# cpu_board.net
KiCad netlist of a schematic drawn in EAGLE
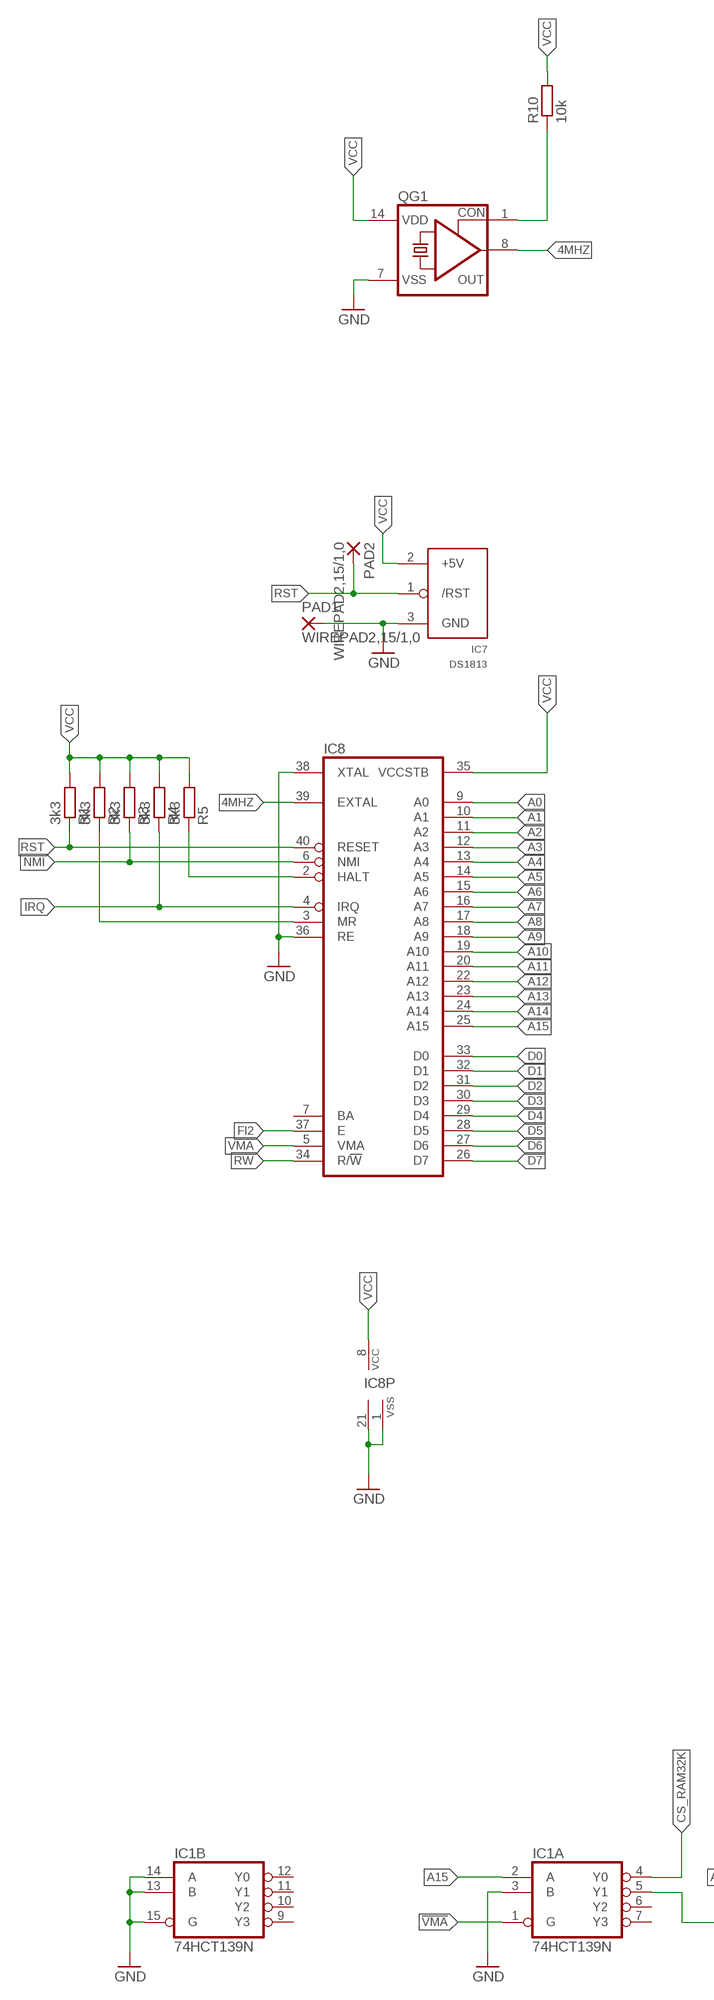
[diagram p0: schematic, sheet 1, part 1 of 2]
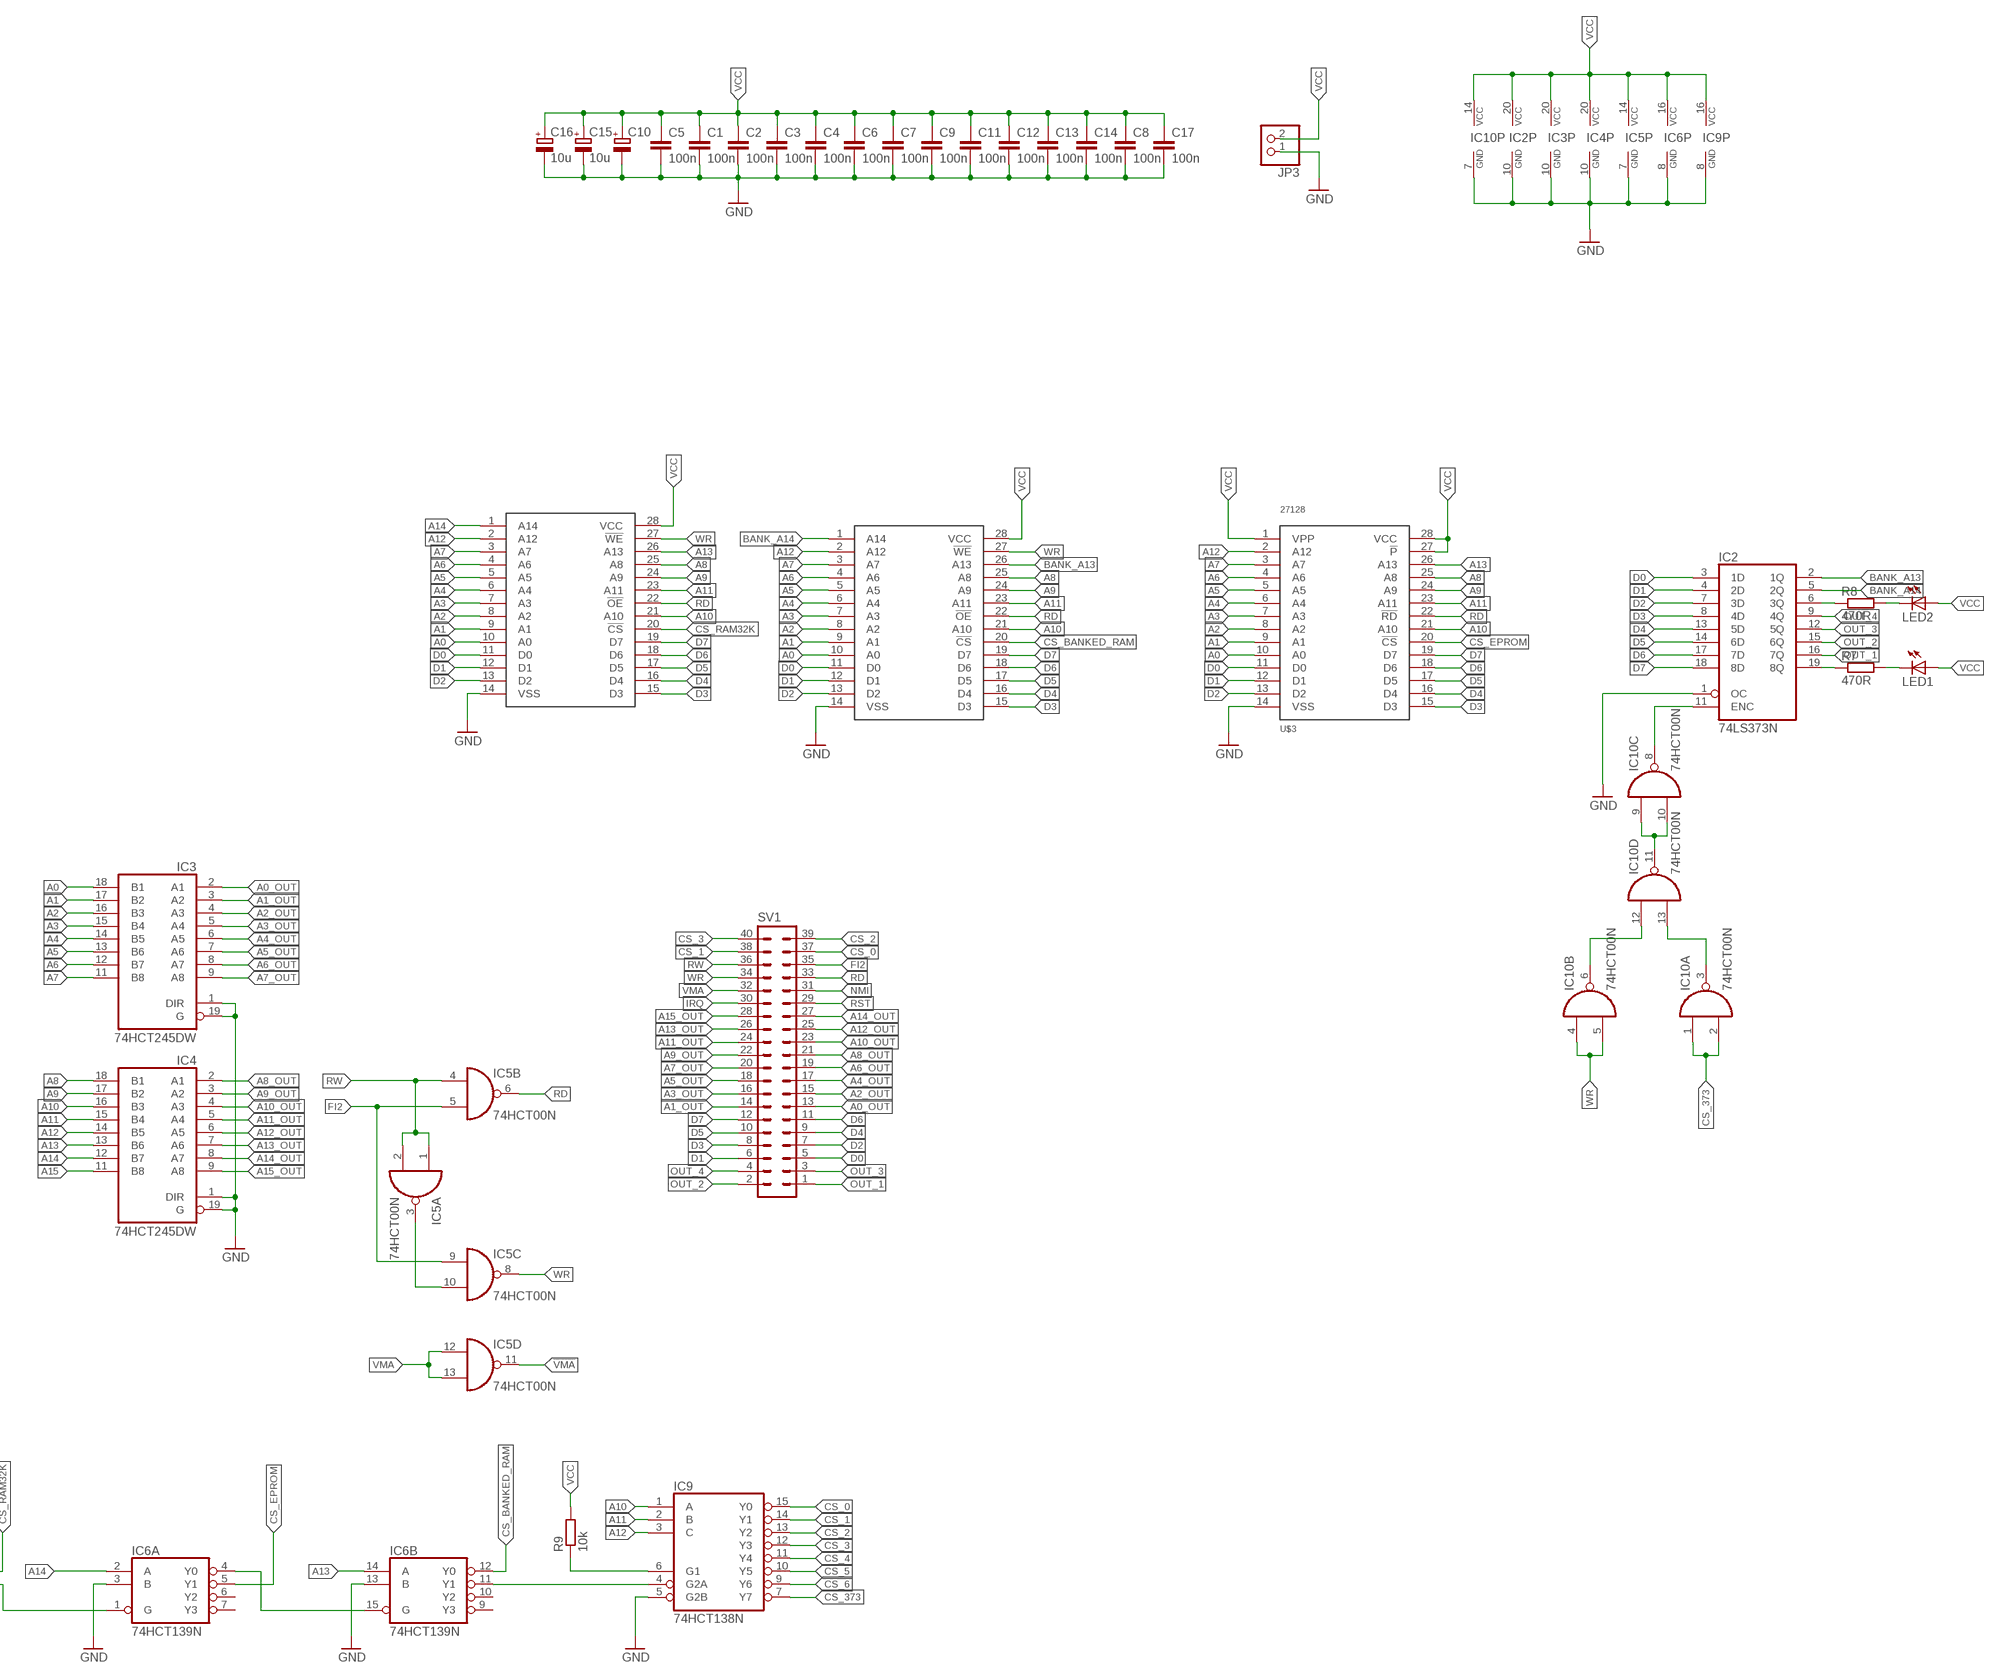
[diagram p1: schematic, sheet 1, part 2 of 2]

(export (version "E")
  (design (tool "Eeschema 10.0.6"))
  (components
    (comp (ref "C1")
      (value "100n")
      (footprint "eagle-import:C1206")
      (libsource (lib "eagle-import") (part "C-EUC1206"))
    )
    (comp (ref "C2")
      (value "100n")
      (footprint "eagle-import:C1206")
      (libsource (lib "eagle-import") (part "C-EUC1206"))
    )
    (comp (ref "C3")
      (value "100n")
      (footprint "eagle-import:C1206")
      (libsource (lib "eagle-import") (part "C-EUC1206"))
    )
    (comp (ref "C4")
      (value "100n")
      (footprint "eagle-import:C1206")
      (libsource (lib "eagle-import") (part "C-EUC1206"))
    )
    (comp (ref "C5")
      (value "100n")
      (footprint "eagle-import:C0603")
      (libsource (lib "eagle-import") (part "C-EUC0603"))
    )
    (comp (ref "C6")
      (value "100n")
      (footprint "eagle-import:C1206")
      (libsource (lib "eagle-import") (part "C-EUC1206"))
    )
    (comp (ref "C7")
      (value "100n")
      (footprint "eagle-import:C0603")
      (libsource (lib "eagle-import") (part "C-EUC0603"))
    )
    (comp (ref "C8")
      (value "100n")
      (footprint "eagle-import:C1206")
      (libsource (lib "eagle-import") (part "C-EUC1206"))
    )
    (comp (ref "C9")
      (value "100n")
      (footprint "eagle-import:C1206")
      (libsource (lib "eagle-import") (part "C-EUC1206"))
    )
    (comp (ref "C10")
      (value "CPOL-EUE5-10.5")
      (footprint "eagle-import:E5-10,5")
      (libsource (lib "eagle-import") (part "CPOL-EUE5-10.5"))
    )
    (comp (ref "C11")
      (value "100n")
      (footprint "eagle-import:C0805")
      (libsource (lib "eagle-import") (part "C-EUC0805"))
    )
    (comp (ref "C12")
      (value "100n")
      (footprint "eagle-import:C0805")
      (libsource (lib "eagle-import") (part "C-EUC0805"))
    )
    (comp (ref "C13")
      (value "100n")
      (footprint "eagle-import:C0805")
      (libsource (lib "eagle-import") (part "C-EUC0805"))
    )
    (comp (ref "C14")
      (value "100n")
      (footprint "eagle-import:C0603")
      (libsource (lib "eagle-import") (part "C-EUC0603"))
    )
    (comp (ref "C15")
      (value "10u")
      (footprint "eagle-import:SMC_B")
      (libsource (lib "eagle-import") (part "CPOL-EUSMCB"))
    )
    (comp (ref "C16")
      (value "10u")
      (footprint "eagle-import:SMC_B")
      (libsource (lib "eagle-import") (part "CPOL-EUSMCB"))
    )
    (comp (ref "C17")
      (value "100n")
      (footprint "eagle-import:C0805")
      (libsource (lib "eagle-import") (part "C-EUC0805"))
    )
    (comp (ref "IC1")
      (value "74HCT139N")
      (footprint "eagle-import:DIL16")
      (libsource (lib "eagle-import") (part "74139NHCT"))
    )
    (comp (ref "IC2")
      (value "74LS373N")
      (footprint "eagle-import:DIL20")
      (libsource (lib "eagle-import") (part "74373NLS"))
    )
    (comp (ref "IC3")
      (value "74HCT245DW")
      (footprint "eagle-import:SO20W")
      (libsource (lib "eagle-import") (part "74245DWHCT"))
    )
    (comp (ref "IC4")
      (value "74HCT245DW")
      (footprint "eagle-import:SO20W")
      (libsource (lib "eagle-import") (part "74245DWHCT"))
    )
    (comp (ref "IC5")
      (value "74HCT00N")
      (footprint "eagle-import:DIL14")
      (libsource (lib "eagle-import") (part "7400NHCT"))
    )
    (comp (ref "IC6")
      (value "74HCT139N")
      (footprint "eagle-import:DIL16")
      (libsource (lib "eagle-import") (part "74139NHCT"))
    )
    (comp (ref "IC7")
      (value "DS1813")
      (footprint "eagle-import:TO-92")
      (libsource (lib "eagle-import") (part "DS1813"))
    )
    (comp (ref "IC8")
      (value "6802")
      (footprint "eagle-import:DIL40")
      (libsource (lib "eagle-import") (part "6802"))
    )
    (comp (ref "IC9")
      (value "74HCT138N")
      (footprint "eagle-import:DIL16")
      (libsource (lib "eagle-import") (part "74138NHCT"))
    )
    (comp (ref "IC10")
      (value "74HCT00N")
      (footprint "eagle-import:DIL14")
      (libsource (lib "eagle-import") (part "7400NHCT"))
    )
    (comp (ref "JP3")
      (value "PINHD-1X2/90")
      (footprint "eagle-import:1X02_90")
      (libsource (lib "eagle-import") (part "PINHD-1X2/90"))
    )
    (comp (ref "LED1")
      (value "LED5MM")
      (footprint "eagle-import:LED5MM")
      (libsource (lib "eagle-import") (part "LED5MM"))
    )
    (comp (ref "LED2")
      (value "LED5MM")
      (footprint "eagle-import:LED5MM")
      (libsource (lib "eagle-import") (part "LED5MM"))
    )
    (comp (ref "PAD1")
      (value "WIREPAD2,15/1,0")
      (footprint "eagle-import:2,15_1,0")
      (libsource (lib "eagle-import") (part "WIREPAD2,15/1,0"))
    )
    (comp (ref "PAD2")
      (value "WIREPAD2,15/1,0")
      (footprint "eagle-import:2,15_1,0")
      (libsource (lib "eagle-import") (part "WIREPAD2,15/1,0"))
    )
    (comp (ref "QG1")
      (value "CRYSTAL_RES-SG51")
      (footprint "eagle-import:SG51")
      (libsource (lib "eagle-import") (part "CRYSTAL_RES-SG51"))
    )
    (comp (ref "R1")
      (value "3k3")
      (footprint "eagle-import:R1206")
      (libsource (lib "eagle-import") (part "R-EU_R1206"))
    )
    (comp (ref "R2")
      (value "3k3")
      (footprint "eagle-import:R1206")
      (libsource (lib "eagle-import") (part "R-EU_R1206"))
    )
    (comp (ref "R3")
      (value "3k3")
      (footprint "eagle-import:R1206")
      (libsource (lib "eagle-import") (part "R-EU_R1206"))
    )
    (comp (ref "R4")
      (value "3k3")
      (footprint "eagle-import:R0603")
      (libsource (lib "eagle-import") (part "R-EU_R0603"))
    )
    (comp (ref "R5")
      (value "3k3")
      (footprint "eagle-import:R1206")
      (libsource (lib "eagle-import") (part "R-EU_R1206"))
    )
    (comp (ref "R7")
      (value "470R")
      (footprint "eagle-import:R1206")
      (libsource (lib "eagle-import") (part "R-EU_R1206"))
    )
    (comp (ref "R8")
      (value "470R")
      (footprint "eagle-import:R1206")
      (libsource (lib "eagle-import") (part "R-EU_R1206"))
    )
    (comp (ref "R9")
      (value "10k")
      (footprint "eagle-import:0204_7")
      (libsource (lib "eagle-import") (part "R-EU_0204/7"))
    )
    (comp (ref "R10")
      (value "10k")
      (footprint "eagle-import:R1206")
      (libsource (lib "eagle-import") (part "R-EU_R1206"))
    )
    (comp (ref "SV1")
      (value "ML40L")
      (footprint "eagle-import:ML40L")
      (libsource (lib "eagle-import") (part "ML40L"))
    )
    (comp (ref "U$2")
      (value "62256")
      (footprint "eagle-import:DIL28-6")
      (libsource (lib "eagle-import") (part "62256"))
    )
    (comp (ref "U$3")
      (value "27128")
      (footprint "eagle-import:DIL28")
      (libsource (lib "eagle-import") (part "27128"))
    )
    (comp (ref "U$4")
      (value "62256")
      (footprint "eagle-import:DIL28-6")
      (libsource (lib "eagle-import") (part "62256"))
    )
  )
  (nets
    (net (code "1") (name "/~{VMA}") (class "Default")
      (node (ref "IC1") (pin "1") (pinfunction "G_1") (pintype "input"))
      (node (ref "IC5") (pin "11") (pinfunction "O_11") (pintype "output"))
    )
    (net (code "2") (name "4MHZ") (class "Default")
      (node (ref "IC8") (pin "39") (pinfunction "EXTAL_39") (pintype "input"))
      (node (ref "QG1") (pin "8") (pinfunction "OUT_8") (pintype "output"))
    )
    (net (code "3") (name "A0") (class "Default")
      (node (ref "IC3") (pin "18") (pinfunction "B1_18") (pintype "bidirectional"))
      (node (ref "IC8") (pin "9") (pinfunction "A0_9") (pintype "output"))
      (node (ref "U$2") (pin "10") (pinfunction "A0_10") (pintype "bidirectional"))
      (node (ref "U$3") (pin "10") (pinfunction "A0_10") (pintype "bidirectional"))
      (node (ref "U$4") (pin "10") (pinfunction "A0_10") (pintype "bidirectional"))
    )
    (net (code "4") (name "A0_OUT") (class "Default")
      (node (ref "IC3") (pin "2") (pinfunction "A1_2") (pintype "bidirectional"))
      (node (ref "SV1") (pin "13") (pinfunction "13_13") (pintype "passive"))
    )
    (net (code "5") (name "A1") (class "Default")
      (node (ref "IC3") (pin "17") (pinfunction "B2_17") (pintype "bidirectional"))
      (node (ref "IC8") (pin "10") (pinfunction "A1_10") (pintype "output"))
      (node (ref "U$2") (pin "9") (pinfunction "A1_9") (pintype "bidirectional"))
      (node (ref "U$3") (pin "9") (pinfunction "A1_9") (pintype "bidirectional"))
      (node (ref "U$4") (pin "9") (pinfunction "A1_9") (pintype "bidirectional"))
    )
    (net (code "6") (name "A1_OUT") (class "Default")
      (node (ref "IC3") (pin "3") (pinfunction "A2_3") (pintype "bidirectional"))
      (node (ref "SV1") (pin "14") (pinfunction "14_14") (pintype "passive"))
    )
    (net (code "7") (name "A2") (class "Default")
      (node (ref "IC3") (pin "16") (pinfunction "B3_16") (pintype "bidirectional"))
      (node (ref "IC8") (pin "11") (pinfunction "A2_11") (pintype "output"))
      (node (ref "U$2") (pin "8") (pinfunction "A2_8") (pintype "bidirectional"))
      (node (ref "U$3") (pin "8") (pinfunction "A2_8") (pintype "bidirectional"))
      (node (ref "U$4") (pin "8") (pinfunction "A2_8") (pintype "bidirectional"))
    )
    (net (code "8") (name "A2_OUT") (class "Default")
      (node (ref "IC3") (pin "4") (pinfunction "A3_4") (pintype "bidirectional"))
      (node (ref "SV1") (pin "15") (pinfunction "15_15") (pintype "passive"))
    )
    (net (code "9") (name "A3") (class "Default")
      (node (ref "IC3") (pin "15") (pinfunction "B4_15") (pintype "bidirectional"))
      (node (ref "IC8") (pin "12") (pinfunction "A3_12") (pintype "output"))
      (node (ref "U$2") (pin "7") (pinfunction "A3_7") (pintype "bidirectional"))
      (node (ref "U$3") (pin "7") (pinfunction "A3_7") (pintype "bidirectional"))
      (node (ref "U$4") (pin "7") (pinfunction "A3_7") (pintype "bidirectional"))
    )
    (net (code "10") (name "A3_OUT") (class "Default")
      (node (ref "IC3") (pin "5") (pinfunction "A4_5") (pintype "bidirectional"))
      (node (ref "SV1") (pin "16") (pinfunction "16_16") (pintype "passive"))
    )
    (net (code "11") (name "A4") (class "Default")
      (node (ref "IC3") (pin "14") (pinfunction "B5_14") (pintype "bidirectional"))
      (node (ref "IC8") (pin "13") (pinfunction "A4_13") (pintype "output"))
      (node (ref "U$2") (pin "6") (pinfunction "A4_6") (pintype "bidirectional"))
      (node (ref "U$3") (pin "6") (pinfunction "A4_6") (pintype "bidirectional"))
      (node (ref "U$4") (pin "6") (pinfunction "A4_6") (pintype "bidirectional"))
    )
    (net (code "12") (name "A4_OUT") (class "Default")
      (node (ref "IC3") (pin "6") (pinfunction "A5_6") (pintype "bidirectional"))
      (node (ref "SV1") (pin "17") (pinfunction "17_17") (pintype "passive"))
    )
    (net (code "13") (name "A5") (class "Default")
      (node (ref "IC3") (pin "13") (pinfunction "B6_13") (pintype "bidirectional"))
      (node (ref "IC8") (pin "14") (pinfunction "A5_14") (pintype "output"))
      (node (ref "U$2") (pin "5") (pinfunction "A5_5") (pintype "bidirectional"))
      (node (ref "U$3") (pin "5") (pinfunction "A5_5") (pintype "bidirectional"))
      (node (ref "U$4") (pin "5") (pinfunction "A5_5") (pintype "bidirectional"))
    )
    (net (code "14") (name "A5_OUT") (class "Default")
      (node (ref "IC3") (pin "7") (pinfunction "A6_7") (pintype "bidirectional"))
      (node (ref "SV1") (pin "18") (pinfunction "18_18") (pintype "passive"))
    )
    (net (code "15") (name "A6") (class "Default")
      (node (ref "IC3") (pin "12") (pinfunction "B7_12") (pintype "bidirectional"))
      (node (ref "IC8") (pin "15") (pinfunction "A6_15") (pintype "output"))
      (node (ref "U$2") (pin "4") (pinfunction "A6_4") (pintype "bidirectional"))
      (node (ref "U$3") (pin "4") (pinfunction "A6_4") (pintype "bidirectional"))
      (node (ref "U$4") (pin "4") (pinfunction "A6_4") (pintype "bidirectional"))
    )
    (net (code "16") (name "A6_OUT") (class "Default")
      (node (ref "IC3") (pin "8") (pinfunction "A7_8") (pintype "bidirectional"))
      (node (ref "SV1") (pin "19") (pinfunction "19_19") (pintype "passive"))
    )
    (net (code "17") (name "A7") (class "Default")
      (node (ref "IC3") (pin "11") (pinfunction "B8_11") (pintype "bidirectional"))
      (node (ref "IC8") (pin "16") (pinfunction "A7_16") (pintype "output"))
      (node (ref "U$2") (pin "3") (pinfunction "A7_3") (pintype "bidirectional"))
      (node (ref "U$3") (pin "3") (pinfunction "A7_3") (pintype "bidirectional"))
      (node (ref "U$4") (pin "3") (pinfunction "A7_3") (pintype "bidirectional"))
    )
    (net (code "18") (name "A7_OUT") (class "Default")
      (node (ref "IC3") (pin "9") (pinfunction "A8_9") (pintype "bidirectional"))
      (node (ref "SV1") (pin "20") (pinfunction "20_20") (pintype "passive"))
    )
    (net (code "19") (name "A8") (class "Default")
      (node (ref "IC4") (pin "18") (pinfunction "B1_18") (pintype "bidirectional"))
      (node (ref "IC8") (pin "17") (pinfunction "A8_17") (pintype "output"))
      (node (ref "U$2") (pin "25") (pinfunction "A8_25") (pintype "bidirectional"))
      (node (ref "U$3") (pin "25") (pinfunction "A8_25") (pintype "bidirectional"))
      (node (ref "U$4") (pin "25") (pinfunction "A8_25") (pintype "bidirectional"))
    )
    (net (code "20") (name "A8_OUT") (class "Default")
      (node (ref "IC4") (pin "2") (pinfunction "A1_2") (pintype "bidirectional"))
      (node (ref "SV1") (pin "21") (pinfunction "21_21") (pintype "passive"))
    )
    (net (code "21") (name "A9") (class "Default")
      (node (ref "IC4") (pin "17") (pinfunction "B2_17") (pintype "bidirectional"))
      (node (ref "IC8") (pin "18") (pinfunction "A9_18") (pintype "output"))
      (node (ref "U$2") (pin "24") (pinfunction "A9_24") (pintype "bidirectional"))
      (node (ref "U$3") (pin "24") (pinfunction "A9_24") (pintype "bidirectional"))
      (node (ref "U$4") (pin "24") (pinfunction "A9_24") (pintype "bidirectional"))
    )
    (net (code "22") (name "A9_OUT") (class "Default")
      (node (ref "IC4") (pin "3") (pinfunction "A2_3") (pintype "bidirectional"))
      (node (ref "SV1") (pin "22") (pinfunction "22_22") (pintype "passive"))
    )
    (net (code "23") (name "A10") (class "Default")
      (node (ref "IC4") (pin "16") (pinfunction "B3_16") (pintype "bidirectional"))
      (node (ref "IC8") (pin "19") (pinfunction "A10_19") (pintype "output"))
      (node (ref "IC9") (pin "1") (pinfunction "A_1") (pintype "input"))
      (node (ref "U$2") (pin "21") (pinfunction "A10_21") (pintype "bidirectional"))
      (node (ref "U$3") (pin "21") (pinfunction "A10_21") (pintype "bidirectional"))
      (node (ref "U$4") (pin "21") (pinfunction "A10_21") (pintype "bidirectional"))
    )
    (net (code "24") (name "A10_OUT") (class "Default")
      (node (ref "IC4") (pin "4") (pinfunction "A3_4") (pintype "bidirectional"))
      (node (ref "SV1") (pin "23") (pinfunction "23_23") (pintype "passive"))
    )
    (net (code "25") (name "A11") (class "Default")
      (node (ref "IC4") (pin "15") (pinfunction "B4_15") (pintype "bidirectional"))
      (node (ref "IC8") (pin "20") (pinfunction "A11_20") (pintype "output"))
      (node (ref "IC9") (pin "2") (pinfunction "B_2") (pintype "input"))
      (node (ref "U$2") (pin "23") (pinfunction "A11_23") (pintype "bidirectional"))
      (node (ref "U$3") (pin "23") (pinfunction "A11_23") (pintype "bidirectional"))
      (node (ref "U$4") (pin "23") (pinfunction "A11_23") (pintype "bidirectional"))
    )
    (net (code "26") (name "A11_OUT") (class "Default")
      (node (ref "IC4") (pin "5") (pinfunction "A4_5") (pintype "bidirectional"))
      (node (ref "SV1") (pin "24") (pinfunction "24_24") (pintype "passive"))
    )
    (net (code "27") (name "A12") (class "Default")
      (node (ref "IC4") (pin "14") (pinfunction "B5_14") (pintype "bidirectional"))
      (node (ref "IC8") (pin "22") (pinfunction "A12_22") (pintype "output"))
      (node (ref "IC9") (pin "3") (pinfunction "C_3") (pintype "input"))
      (node (ref "U$2") (pin "2") (pinfunction "A12_2") (pintype "bidirectional"))
      (node (ref "U$3") (pin "2") (pinfunction "A12_2") (pintype "bidirectional"))
      (node (ref "U$4") (pin "2") (pinfunction "A12_2") (pintype "bidirectional"))
    )
    (net (code "28") (name "A12_OUT") (class "Default")
      (node (ref "IC4") (pin "6") (pinfunction "A5_6") (pintype "bidirectional"))
      (node (ref "SV1") (pin "25") (pinfunction "25_25") (pintype "passive"))
    )
    (net (code "29") (name "A13") (class "Default")
      (node (ref "IC4") (pin "13") (pinfunction "B6_13") (pintype "bidirectional"))
      (node (ref "IC6") (pin "14") (pinfunction "A_14") (pintype "input"))
      (node (ref "IC8") (pin "23") (pinfunction "A13_23") (pintype "output"))
      (node (ref "U$3") (pin "26") (pinfunction "A13_26") (pintype "bidirectional"))
      (node (ref "U$4") (pin "26") (pinfunction "A13_26") (pintype "bidirectional"))
    )
    (net (code "30") (name "A13_OUT") (class "Default")
      (node (ref "IC4") (pin "7") (pinfunction "A6_7") (pintype "bidirectional"))
      (node (ref "SV1") (pin "26") (pinfunction "26_26") (pintype "passive"))
    )
    (net (code "31") (name "A14") (class "Default")
      (node (ref "IC4") (pin "12") (pinfunction "B7_12") (pintype "bidirectional"))
      (node (ref "IC6") (pin "2") (pinfunction "A_2") (pintype "input"))
      (node (ref "IC8") (pin "24") (pinfunction "A14_24") (pintype "output"))
      (node (ref "U$4") (pin "1") (pinfunction "A14_1") (pintype "bidirectional"))
    )
    (net (code "32") (name "A14_OUT") (class "Default")
      (node (ref "IC4") (pin "8") (pinfunction "A7_8") (pintype "bidirectional"))
      (node (ref "SV1") (pin "27") (pinfunction "27_27") (pintype "passive"))
    )
    (net (code "33") (name "A15") (class "Default")
      (node (ref "IC1") (pin "2") (pinfunction "A_2") (pintype "input"))
      (node (ref "IC4") (pin "11") (pinfunction "B8_11") (pintype "bidirectional"))
      (node (ref "IC8") (pin "25") (pinfunction "A15_25") (pintype "output"))
    )
    (net (code "34") (name "A15_OUT") (class "Default")
      (node (ref "IC4") (pin "9") (pinfunction "A8_9") (pintype "bidirectional"))
      (node (ref "SV1") (pin "28") (pinfunction "28_28") (pintype "passive"))
    )
    (net (code "35") (name "BANK_A13") (class "Default")
      (node (ref "IC2") (pin "2") (pinfunction "1Q_2") (pintype "tri_state"))
      (node (ref "U$2") (pin "26") (pinfunction "A13_26") (pintype "bidirectional"))
    )
    (net (code "36") (name "BANK_A14") (class "Default")
      (node (ref "IC2") (pin "5") (pinfunction "2Q_5") (pintype "tri_state"))
      (node (ref "U$2") (pin "1") (pinfunction "A14_1") (pintype "bidirectional"))
    )
    (net (code "37") (name "CS_0") (class "Default")
      (node (ref "IC9") (pin "15") (pinfunction "Y0_15") (pintype "output"))
      (node (ref "SV1") (pin "37") (pinfunction "37_37") (pintype "passive"))
    )
    (net (code "38") (name "CS_1") (class "Default")
      (node (ref "IC9") (pin "14") (pinfunction "Y1_14") (pintype "output"))
      (node (ref "SV1") (pin "38") (pinfunction "38_38") (pintype "passive"))
    )
    (net (code "39") (name "CS_2") (class "Default")
      (node (ref "IC9") (pin "13") (pinfunction "Y2_13") (pintype "output"))
      (node (ref "SV1") (pin "39") (pinfunction "39_39") (pintype "passive"))
    )
    (net (code "40") (name "CS_3") (class "Default")
      (node (ref "IC9") (pin "12") (pinfunction "Y3_12") (pintype "output"))
      (node (ref "SV1") (pin "40") (pinfunction "40_40") (pintype "passive"))
    )
    (net (code "41") (name "CS_4") (class "Default")
      (node (ref "IC9") (pin "11") (pinfunction "Y4_11") (pintype "output"))
    )
    (net (code "42") (name "CS_5") (class "Default")
      (node (ref "IC9") (pin "10") (pinfunction "Y5_10") (pintype "output"))
    )
    (net (code "43") (name "CS_6") (class "Default")
      (node (ref "IC9") (pin "9") (pinfunction "Y6_9") (pintype "output"))
    )
    (net (code "44") (name "CS_373") (class "Default")
      (node (ref "IC10") (pin "1") (pinfunction "I0_1") (pintype "input"))
      (node (ref "IC10") (pin "2") (pinfunction "I1_2") (pintype "input"))
      (node (ref "IC9") (pin "7") (pinfunction "Y7_7") (pintype "output"))
    )
    (net (code "45") (name "CS_BANKED_RAM") (class "Default")
      (node (ref "IC6") (pin "12") (pinfunction "Y0_12") (pintype "output"))
      (node (ref "U$2") (pin "20") (pinfunction "~{CS}_20") (pintype "bidirectional"))
    )
    (net (code "46") (name "CS_EPROM") (class "Default")
      (node (ref "IC6") (pin "5") (pinfunction "Y1_5") (pintype "output"))
      (node (ref "U$3") (pin "20") (pinfunction "~{CS}_20") (pintype "bidirectional"))
    )
    (net (code "47") (name "CS_RAM32K") (class "Default")
      (node (ref "IC1") (pin "4") (pinfunction "Y0_4") (pintype "output"))
      (node (ref "U$4") (pin "20") (pinfunction "~{CS}_20") (pintype "bidirectional"))
    )
    (net (code "48") (name "D0") (class "Default")
      (node (ref "IC2") (pin "3") (pinfunction "1D_3") (pintype "input"))
      (node (ref "IC8") (pin "33") (pinfunction "D0_33") (pintype "bidirectional"))
      (node (ref "SV1") (pin "5") (pinfunction "5_5") (pintype "passive"))
      (node (ref "U$2") (pin "11") (pinfunction "D0_11") (pintype "bidirectional"))
      (node (ref "U$3") (pin "11") (pinfunction "D0_11") (pintype "bidirectional"))
      (node (ref "U$4") (pin "11") (pinfunction "D0_11") (pintype "bidirectional"))
    )
    (net (code "49") (name "D1") (class "Default")
      (node (ref "IC2") (pin "4") (pinfunction "2D_4") (pintype "input"))
      (node (ref "IC8") (pin "32") (pinfunction "D1_32") (pintype "bidirectional"))
      (node (ref "SV1") (pin "6") (pinfunction "6_6") (pintype "passive"))
      (node (ref "U$2") (pin "12") (pinfunction "D1_12") (pintype "bidirectional"))
      (node (ref "U$3") (pin "12") (pinfunction "D1_12") (pintype "bidirectional"))
      (node (ref "U$4") (pin "12") (pinfunction "D1_12") (pintype "bidirectional"))
    )
    (net (code "50") (name "D2") (class "Default")
      (node (ref "IC2") (pin "7") (pinfunction "3D_7") (pintype "input"))
      (node (ref "IC8") (pin "31") (pinfunction "D2_31") (pintype "bidirectional"))
      (node (ref "SV1") (pin "7") (pinfunction "7_7") (pintype "passive"))
      (node (ref "U$2") (pin "13") (pinfunction "D2_13") (pintype "bidirectional"))
      (node (ref "U$3") (pin "13") (pinfunction "D2_13") (pintype "bidirectional"))
      (node (ref "U$4") (pin "13") (pinfunction "D2_13") (pintype "bidirectional"))
    )
    (net (code "51") (name "D3") (class "Default")
      (node (ref "IC2") (pin "8") (pinfunction "4D_8") (pintype "input"))
      (node (ref "IC8") (pin "30") (pinfunction "D3_30") (pintype "bidirectional"))
      (node (ref "SV1") (pin "8") (pinfunction "8_8") (pintype "passive"))
      (node (ref "U$2") (pin "15") (pinfunction "D3_15") (pintype "bidirectional"))
      (node (ref "U$3") (pin "15") (pinfunction "D3_15") (pintype "bidirectional"))
      (node (ref "U$4") (pin "15") (pinfunction "D3_15") (pintype "bidirectional"))
    )
    (net (code "52") (name "D4") (class "Default")
      (node (ref "IC2") (pin "13") (pinfunction "5D_13") (pintype "input"))
      (node (ref "IC8") (pin "29") (pinfunction "D4_29") (pintype "bidirectional"))
      (node (ref "SV1") (pin "9") (pinfunction "9_9") (pintype "passive"))
      (node (ref "U$2") (pin "16") (pinfunction "D4_16") (pintype "bidirectional"))
      (node (ref "U$3") (pin "16") (pinfunction "D4_16") (pintype "bidirectional"))
      (node (ref "U$4") (pin "16") (pinfunction "D4_16") (pintype "bidirectional"))
    )
    (net (code "53") (name "D5") (class "Default")
      (node (ref "IC2") (pin "14") (pinfunction "6D_14") (pintype "input"))
      (node (ref "IC8") (pin "28") (pinfunction "D5_28") (pintype "bidirectional"))
      (node (ref "SV1") (pin "10") (pinfunction "10_10") (pintype "passive"))
      (node (ref "U$2") (pin "17") (pinfunction "D5_17") (pintype "bidirectional"))
      (node (ref "U$3") (pin "17") (pinfunction "D5_17") (pintype "bidirectional"))
      (node (ref "U$4") (pin "17") (pinfunction "D5_17") (pintype "bidirectional"))
    )
    (net (code "54") (name "D6") (class "Default")
      (node (ref "IC2") (pin "17") (pinfunction "7D_17") (pintype "input"))
      (node (ref "IC8") (pin "27") (pinfunction "D6_27") (pintype "bidirectional"))
      (node (ref "SV1") (pin "11") (pinfunction "11_11") (pintype "passive"))
      (node (ref "U$2") (pin "18") (pinfunction "D6_18") (pintype "bidirectional"))
      (node (ref "U$3") (pin "18") (pinfunction "D6_18") (pintype "bidirectional"))
      (node (ref "U$4") (pin "18") (pinfunction "D6_18") (pintype "bidirectional"))
    )
    (net (code "55") (name "D7") (class "Default")
      (node (ref "IC2") (pin "18") (pinfunction "8D_18") (pintype "input"))
      (node (ref "IC8") (pin "26") (pinfunction "D7_26") (pintype "bidirectional"))
      (node (ref "SV1") (pin "12") (pinfunction "12_12") (pintype "passive"))
      (node (ref "U$2") (pin "19") (pinfunction "D7_19") (pintype "bidirectional"))
      (node (ref "U$3") (pin "19") (pinfunction "D7_19") (pintype "bidirectional"))
      (node (ref "U$4") (pin "19") (pinfunction "D7_19") (pintype "bidirectional"))
    )
    (net (code "56") (name "FI2") (class "Default")
      (node (ref "IC5") (pin "5") (pinfunction "I1_5") (pintype "input"))
      (node (ref "IC5") (pin "9") (pinfunction "I0_9") (pintype "input"))
      (node (ref "IC8") (pin "37") (pinfunction "E_37") (pintype "output"))
      (node (ref "SV1") (pin "35") (pinfunction "35_35") (pintype "passive"))
    )
    (net (code "57") (name "GND") (class "Default")
      (node (ref "C1") (pin "2") (pinfunction "2_2") (pintype "passive"))
      (node (ref "C10") (pin "-") (pinfunction "-_-") (pintype "passive"))
      (node (ref "C11") (pin "2") (pinfunction "2_2") (pintype "passive"))
      (node (ref "C12") (pin "2") (pinfunction "2_2") (pintype "passive"))
      (node (ref "C13") (pin "2") (pinfunction "2_2") (pintype "passive"))
      (node (ref "C14") (pin "2") (pinfunction "2_2") (pintype "passive"))
      (node (ref "C15") (pin "-") (pinfunction "-_-") (pintype "passive"))
      (node (ref "C16") (pin "-") (pinfunction "-_-") (pintype "passive"))
      (node (ref "C17") (pin "2") (pinfunction "2_2") (pintype "passive"))
      (node (ref "C2") (pin "2") (pinfunction "2_2") (pintype "passive"))
      (node (ref "C3") (pin "2") (pinfunction "2_2") (pintype "passive"))
      (node (ref "C4") (pin "2") (pinfunction "2_2") (pintype "passive"))
      (node (ref "C5") (pin "2") (pinfunction "2_2") (pintype "passive"))
      (node (ref "C6") (pin "2") (pinfunction "2_2") (pintype "passive"))
      (node (ref "C7") (pin "2") (pinfunction "2_2") (pintype "passive"))
      (node (ref "C8") (pin "2") (pinfunction "2_2") (pintype "passive"))
      (node (ref "C9") (pin "2") (pinfunction "2_2") (pintype "passive"))
      (node (ref "IC1") (pin "13") (pinfunction "B_13") (pintype "input"))
      (node (ref "IC1") (pin "14") (pinfunction "A_14") (pintype "input"))
      (node (ref "IC1") (pin "15") (pinfunction "G_15") (pintype "input"))
      (node (ref "IC1") (pin "3") (pinfunction "B_3") (pintype "input"))
      (node (ref "IC10") (pin "7") (pinfunction "GND_7") (pintype "power_in"))
      (node (ref "IC2") (pin "1") (pinfunction "OC_1") (pintype "input"))
      (node (ref "IC2") (pin "10") (pinfunction "GND_10") (pintype "power_in"))
      (node (ref "IC3") (pin "1") (pinfunction "DIR_1") (pintype "input"))
      (node (ref "IC3") (pin "10") (pinfunction "GND_10") (pintype "power_in"))
      (node (ref "IC3") (pin "19") (pinfunction "G_19") (pintype "input"))
      (node (ref "IC4") (pin "1") (pinfunction "DIR_1") (pintype "input"))
      (node (ref "IC4") (pin "10") (pinfunction "GND_10") (pintype "power_in"))
      (node (ref "IC4") (pin "19") (pinfunction "G_19") (pintype "input"))
      (node (ref "IC5") (pin "7") (pinfunction "GND_7") (pintype "power_in"))
      (node (ref "IC6") (pin "13") (pinfunction "B_13") (pintype "input"))
      (node (ref "IC6") (pin "3") (pinfunction "B_3") (pintype "input"))
      (node (ref "IC6") (pin "8") (pinfunction "GND_8") (pintype "power_in"))
      (node (ref "IC7") (pin "3") (pinfunction "GND_3") (pintype "power_in"))
      (node (ref "IC8") (pin "1") (pinfunction "VSS_1") (pintype "power_in"))
      (node (ref "IC8") (pin "21") (pinfunction "VSS_21") (pintype "power_in"))
      (node (ref "IC8") (pin "36") (pinfunction "RE_36") (pintype "input"))
      (node (ref "IC8") (pin "38") (pinfunction "XTAL_38") (pintype "input"))
      (node (ref "IC9") (pin "5") (pinfunction "G2B_5") (pintype "input"))
      (node (ref "IC9") (pin "8") (pinfunction "GND_8") (pintype "power_in"))
      (node (ref "JP3") (pin "1") (pinfunction "1_1") (pintype "passive"))
      (node (ref "PAD1") (pin "1") (pinfunction "P_1") (pintype "passive"))
      (node (ref "QG1") (pin "7") (pinfunction "VSS_7") (pintype "power_in"))
      (node (ref "U$2") (pin "14") (pinfunction "VSS_14") (pintype "bidirectional"))
      (node (ref "U$3") (pin "14") (pinfunction "VSS_14") (pintype "bidirectional"))
      (node (ref "U$4") (pin "14") (pinfunction "VSS_14") (pintype "bidirectional"))
    )
    (net (code "58") (name "IRQ") (class "Default")
      (node (ref "IC8") (pin "4") (pinfunction "IRQ_4") (pintype "input"))
      (node (ref "R4") (pin "1") (pinfunction "1_1") (pintype "passive"))
      (node (ref "SV1") (pin "30") (pinfunction "30_30") (pintype "passive"))
    )
    (net (code "59") (name "NMI") (class "Default")
      (node (ref "IC8") (pin "6") (pinfunction "NMI_6") (pintype "input"))
      (node (ref "R3") (pin "1") (pinfunction "1_1") (pintype "passive"))
      (node (ref "SV1") (pin "31") (pinfunction "31_31") (pintype "passive"))
    )
    (net (code "60") (name "Net-(IC1A-Y1)") (class "Default")
      (node (ref "IC1") (pin "5") (pinfunction "Y1_5") (pintype "output"))
      (node (ref "IC6") (pin "1") (pinfunction "G_1") (pintype "input"))
    )
    (net (code "61") (name "Net-(IC2A-3Q)") (class "Default")
      (node (ref "IC2") (pin "6") (pinfunction "3Q_6") (pintype "tri_state"))
      (node (ref "R8") (pin "1") (pinfunction "1_1") (pintype "passive"))
    )
    (net (code "62") (name "Net-(IC2A-8Q)") (class "Default")
      (node (ref "IC2") (pin "19") (pinfunction "8Q_19") (pintype "tri_state"))
      (node (ref "R7") (pin "1") (pinfunction "1_1") (pintype "passive"))
    )
    (net (code "63") (name "Net-(IC5A-O)") (class "Default")
      (node (ref "IC5") (pin "10") (pinfunction "I1_10") (pintype "input"))
      (node (ref "IC5") (pin "3") (pinfunction "O_3") (pintype "output"))
    )
    (net (code "64") (name "Net-(IC6A-Y0)") (class "Default")
      (node (ref "IC6") (pin "15") (pinfunction "G_15") (pintype "input"))
      (node (ref "IC6") (pin "4") (pinfunction "Y0_4") (pintype "output"))
    )
    (net (code "65") (name "Net-(IC6B-Y1)") (class "Default")
      (node (ref "IC6") (pin "11") (pinfunction "Y1_11") (pintype "output"))
      (node (ref "IC9") (pin "4") (pinfunction "G2A_4") (pintype "input"))
    )
    (net (code "66") (name "Net-(IC8A-HALT)") (class "Default")
      (node (ref "IC8") (pin "2") (pinfunction "HALT_2") (pintype "input"))
      (node (ref "R5") (pin "1") (pinfunction "1_1") (pintype "passive"))
    )
    (net (code "67") (name "Net-(IC8A-MR)") (class "Default")
      (node (ref "IC8") (pin "3") (pinfunction "MR_3") (pintype "input"))
      (node (ref "R2") (pin "1") (pinfunction "1_1") (pintype "passive"))
    )
    (net (code "68") (name "Net-(IC9A-G1)") (class "Default")
      (node (ref "IC9") (pin "6") (pinfunction "G1_6") (pintype "input"))
      (node (ref "R9") (pin "1") (pinfunction "1_1") (pintype "passive"))
    )
    (net (code "69") (name "Net-(IC10A-O)") (class "Default")
      (node (ref "IC10") (pin "13") (pinfunction "I1_13") (pintype "input"))
      (node (ref "IC10") (pin "3") (pinfunction "O_3") (pintype "output"))
    )
    (net (code "70") (name "Net-(IC10B-O)") (class "Default")
      (node (ref "IC10") (pin "12") (pinfunction "I0_12") (pintype "input"))
      (node (ref "IC10") (pin "6") (pinfunction "O_6") (pintype "output"))
    )
    (net (code "71") (name "Net-(IC10C-I0)") (class "Default")
      (node (ref "IC10") (pin "10") (pinfunction "I1_10") (pintype "input"))
      (node (ref "IC10") (pin "11") (pinfunction "O_11") (pintype "output"))
      (node (ref "IC10") (pin "9") (pinfunction "I0_9") (pintype "input"))
    )
    (net (code "72") (name "Net-(IC10C-O)") (class "Default")
      (node (ref "IC10") (pin "8") (pinfunction "O_8") (pintype "output"))
      (node (ref "IC2") (pin "11") (pinfunction "ENC_11") (pintype "input"))
    )
    (net (code "73") (name "Net-(LED1-C)") (class "Default")
      (node (ref "LED1") (pin "K") (pinfunction "C_K") (pintype "passive"))
      (node (ref "R7") (pin "2") (pinfunction "2_2") (pintype "passive"))
    )
    (net (code "74") (name "Net-(LED2-C)") (class "Default")
      (node (ref "LED2") (pin "K") (pinfunction "C_K") (pintype "passive"))
      (node (ref "R8") (pin "2") (pinfunction "2_2") (pintype "passive"))
    )
    (net (code "75") (name "Net-(QG1-CON)") (class "Default")
      (node (ref "QG1") (pin "1") (pinfunction "CON_1") (pintype "input"))
      (node (ref "R10") (pin "1") (pinfunction "1_1") (pintype "passive"))
    )
    (net (code "76") (name "OUT_1") (class "Default")
      (node (ref "IC2") (pin "16") (pinfunction "7Q_16") (pintype "tri_state"))
      (node (ref "SV1") (pin "1") (pinfunction "1_1") (pintype "passive"))
    )
    (net (code "77") (name "OUT_2") (class "Default")
      (node (ref "IC2") (pin "15") (pinfunction "6Q_15") (pintype "tri_state"))
      (node (ref "SV1") (pin "2") (pinfunction "2_2") (pintype "passive"))
    )
    (net (code "78") (name "OUT_3") (class "Default")
      (node (ref "IC2") (pin "12") (pinfunction "5Q_12") (pintype "tri_state"))
      (node (ref "SV1") (pin "3") (pinfunction "3_3") (pintype "passive"))
    )
    (net (code "79") (name "OUT_4") (class "Default")
      (node (ref "IC2") (pin "9") (pinfunction "4Q_9") (pintype "tri_state"))
      (node (ref "SV1") (pin "4") (pinfunction "4_4") (pintype "passive"))
    )
    (net (code "80") (name "RD") (class "Default")
      (node (ref "IC5") (pin "6") (pinfunction "O_6") (pintype "output"))
      (node (ref "SV1") (pin "33") (pinfunction "33_33") (pintype "passive"))
      (node (ref "U$2") (pin "22") (pinfunction "~{OE}_22") (pintype "bidirectional"))
      (node (ref "U$3") (pin "22") (pinfunction "~{RD}_22") (pintype "bidirectional"))
      (node (ref "U$4") (pin "22") (pinfunction "~{OE}_22") (pintype "bidirectional"))
    )
    (net (code "81") (name "RST") (class "Default")
      (node (ref "IC7") (pin "1") (pinfunction "/RST_1") (pintype "passive"))
      (node (ref "IC8") (pin "40") (pinfunction "RESET_40") (pintype "input"))
      (node (ref "PAD2") (pin "1") (pinfunction "P_1") (pintype "passive"))
      (node (ref "R1") (pin "1") (pinfunction "1_1") (pintype "passive"))
      (node (ref "SV1") (pin "29") (pinfunction "29_29") (pintype "passive"))
    )
    (net (code "82") (name "RW") (class "Default")
      (node (ref "IC5") (pin "1") (pinfunction "I0_1") (pintype "input"))
      (node (ref "IC5") (pin "2") (pinfunction "I1_2") (pintype "input"))
      (node (ref "IC5") (pin "4") (pinfunction "I0_4") (pintype "input"))
      (node (ref "IC8") (pin "34") (pinfunction "R/~{W}_34") (pintype "output"))
      (node (ref "SV1") (pin "36") (pinfunction "36_36") (pintype "passive"))
    )
    (net (code "83") (name "VCC") (class "Default")
      (node (ref "C1") (pin "1") (pinfunction "1_1") (pintype "passive"))
      (node (ref "C10") (pin "+") (pinfunction "+_+") (pintype "passive"))
      (node (ref "C11") (pin "1") (pinfunction "1_1") (pintype "passive"))
      (node (ref "C12") (pin "1") (pinfunction "1_1") (pintype "passive"))
      (node (ref "C13") (pin "1") (pinfunction "1_1") (pintype "passive"))
      (node (ref "C14") (pin "1") (pinfunction "1_1") (pintype "passive"))
      (node (ref "C15") (pin "+") (pinfunction "+_+") (pintype "passive"))
      (node (ref "C16") (pin "+") (pinfunction "+_+") (pintype "passive"))
      (node (ref "C17") (pin "1") (pinfunction "1_1") (pintype "passive"))
      (node (ref "C2") (pin "1") (pinfunction "1_1") (pintype "passive"))
      (node (ref "C3") (pin "1") (pinfunction "1_1") (pintype "passive"))
      (node (ref "C4") (pin "1") (pinfunction "1_1") (pintype "passive"))
      (node (ref "C5") (pin "1") (pinfunction "1_1") (pintype "passive"))
      (node (ref "C6") (pin "1") (pinfunction "1_1") (pintype "passive"))
      (node (ref "C7") (pin "1") (pinfunction "1_1") (pintype "passive"))
      (node (ref "C8") (pin "1") (pinfunction "1_1") (pintype "passive"))
      (node (ref "C9") (pin "1") (pinfunction "1_1") (pintype "passive"))
      (node (ref "IC10") (pin "14") (pinfunction "VCC_14") (pintype "power_in"))
      (node (ref "IC2") (pin "20") (pinfunction "VCC_20") (pintype "power_in"))
      (node (ref "IC3") (pin "20") (pinfunction "VCC_20") (pintype "power_in"))
      (node (ref "IC4") (pin "20") (pinfunction "VCC_20") (pintype "power_in"))
      (node (ref "IC5") (pin "14") (pinfunction "VCC_14") (pintype "power_in"))
      (node (ref "IC6") (pin "16") (pinfunction "VCC_16") (pintype "power_in"))
      (node (ref "IC7") (pin "2") (pinfunction "+5V_2") (pintype "power_in"))
      (node (ref "IC8") (pin "35") (pinfunction "VCCSTB_35") (pintype "input"))
      (node (ref "IC8") (pin "8") (pinfunction "VCC_8") (pintype "power_in"))
      (node (ref "IC9") (pin "16") (pinfunction "VCC_16") (pintype "power_in"))
      (node (ref "JP3") (pin "2") (pinfunction "2_2") (pintype "passive"))
      (node (ref "LED1") (pin "A") (pinfunction "A_A") (pintype "passive"))
      (node (ref "LED2") (pin "A") (pinfunction "A_A") (pintype "passive"))
      (node (ref "QG1") (pin "14") (pinfunction "VDD_14") (pintype "power_in"))
      (node (ref "R1") (pin "2") (pinfunction "2_2") (pintype "passive"))
      (node (ref "R10") (pin "2") (pinfunction "2_2") (pintype "passive"))
      (node (ref "R2") (pin "2") (pinfunction "2_2") (pintype "passive"))
      (node (ref "R3") (pin "2") (pinfunction "2_2") (pintype "passive"))
      (node (ref "R4") (pin "2") (pinfunction "2_2") (pintype "passive"))
      (node (ref "R5") (pin "2") (pinfunction "2_2") (pintype "passive"))
      (node (ref "R9") (pin "2") (pinfunction "2_2") (pintype "passive"))
      (node (ref "U$2") (pin "28") (pinfunction "VCC_28") (pintype "bidirectional"))
      (node (ref "U$3") (pin "1") (pinfunction "VPP_1") (pintype "bidirectional"))
      (node (ref "U$3") (pin "27") (pinfunction "~{P}_27") (pintype "bidirectional"))
      (node (ref "U$3") (pin "28") (pinfunction "VCC_28") (pintype "bidirectional"))
      (node (ref "U$4") (pin "28") (pinfunction "VCC_28") (pintype "bidirectional"))
    )
    (net (code "84") (name "VMA") (class "Default")
      (node (ref "IC5") (pin "12") (pinfunction "I0_12") (pintype "input"))
      (node (ref "IC5") (pin "13") (pinfunction "I1_13") (pintype "input"))
      (node (ref "IC8") (pin "5") (pinfunction "VMA_5") (pintype "output"))
      (node (ref "SV1") (pin "32") (pinfunction "32_32") (pintype "passive"))
    )
    (net (code "85") (name "WR") (class "Default")
      (node (ref "IC10") (pin "4") (pinfunction "I0_4") (pintype "input"))
      (node (ref "IC10") (pin "5") (pinfunction "I1_5") (pintype "input"))
      (node (ref "IC5") (pin "8") (pinfunction "O_8") (pintype "output"))
      (node (ref "SV1") (pin "34") (pinfunction "34_34") (pintype "passive"))
      (node (ref "U$2") (pin "27") (pinfunction "~{WE}_27") (pintype "bidirectional"))
      (node (ref "U$4") (pin "27") (pinfunction "~{WE}_27") (pintype "bidirectional"))
    )
    (net (code "86") (name "unconnected-(IC1A-Y2-Pad6)") (class "Default")
      (node (ref "IC1") (pin "6") (pinfunction "Y2_6") (pintype "output"))
    )
    (net (code "87") (name "unconnected-(IC1A-Y3-Pad7)") (class "Default")
      (node (ref "IC1") (pin "7") (pinfunction "Y3_7") (pintype "output"))
    )
    (net (code "88") (name "unconnected-(IC1B-Y0-Pad12)") (class "Default")
      (node (ref "IC1") (pin "12") (pinfunction "Y0_12") (pintype "output"))
    )
    (net (code "89") (name "unconnected-(IC1B-Y1-Pad11)") (class "Default")
      (node (ref "IC1") (pin "11") (pinfunction "Y1_11") (pintype "output"))
    )
    (net (code "90") (name "unconnected-(IC1B-Y2-Pad10)") (class "Default")
      (node (ref "IC1") (pin "10") (pinfunction "Y2_10") (pintype "output"))
    )
    (net (code "91") (name "unconnected-(IC1B-Y3-Pad9)") (class "Default")
      (node (ref "IC1") (pin "9") (pinfunction "Y3_9") (pintype "output"))
    )
    (net (code "92") (name "unconnected-(IC6A-Y2-Pad6)") (class "Default")
      (node (ref "IC6") (pin "6") (pinfunction "Y2_6") (pintype "output"))
    )
    (net (code "93") (name "unconnected-(IC6A-Y3-Pad7)") (class "Default")
      (node (ref "IC6") (pin "7") (pinfunction "Y3_7") (pintype "output"))
    )
    (net (code "94") (name "unconnected-(IC6B-Y2-Pad10)") (class "Default")
      (node (ref "IC6") (pin "10") (pinfunction "Y2_10") (pintype "output"))
    )
    (net (code "95") (name "unconnected-(IC6B-Y3-Pad9)") (class "Default")
      (node (ref "IC6") (pin "9") (pinfunction "Y3_9") (pintype "output"))
    )
    (net (code "96") (name "unconnected-(IC8A-BA-Pad7)") (class "Default")
      (node (ref "IC8") (pin "7") (pinfunction "BA_7") (pintype "output"))
    )
  )
)
